# Power.net
KiCad netlist of a schematic drawn in Altium Designer
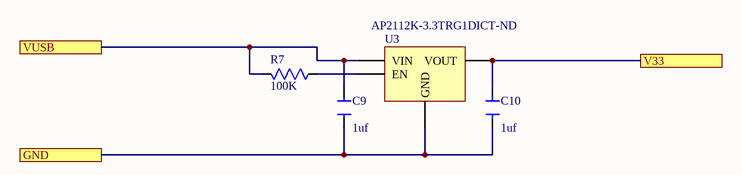
[diagram p0: Power.SchDoc]

(export (version "E")
  (design (tool "Eeschema 10.0.6"))
  (components
    (comp (ref "C9")
      (value "1uf")
      (footprint "CAP_0402")
      (fields (field (name "Comment") "Cap"))
      (libsource (lib "ZGR") (part "Cap"))
    )
    (comp (ref "C10")
      (value "1uf")
      (footprint "CAP_0402")
      (fields (field (name "Comment") "Cap"))
      (libsource (lib "ZGR") (part "Cap"))
    )
    (comp (ref "R7")
      (value "100K")
      (footprint "RES_0402")
      (fields (field (name "Comment") "Res"))
      (libsource (lib "ZGR") (part "Res"))
    )
    (comp (ref "U3")
      (value "AP2112K-3.3TRG1")
      (footprint "SOT23-5")
      (description "IC REG LINEAR 3.3V 600MA SOT23-5")
      (fields
        (field (name "MANUFACTURER") "Diodes")
        (field (name "SUPPLIER PART NUMBER 1") "AP2112K-3.3TRG1DICT-ND")
      )
      (libsource (lib "ZGR") (part "AP2112K-3.3TRG1"))
    )
  )
  (nets
    (net (code "1") (name "/GND") (class "Default")
      (node (ref "C10") (pin "2") (pinfunction "2_2") (pintype "passive"))
      (node (ref "C9") (pin "2") (pinfunction "2_2") (pintype "passive"))
      (node (ref "U3") (pin "3") (pinfunction "GND_3") (pintype "power_in"))
    )
    (net (code "2") (name "/V33") (class "Default")
      (node (ref "C10") (pin "1") (pinfunction "1_1") (pintype "passive"))
      (node (ref "U3") (pin "4") (pinfunction "VOUT_4") (pintype "power_in"))
    )
    (net (code "3") (name "/VUSB") (class "Default")
      (node (ref "C9") (pin "1") (pinfunction "1_1") (pintype "passive"))
      (node (ref "R7") (pin "1") (pinfunction "1_1") (pintype "passive"))
      (node (ref "U3") (pin "1") (pinfunction "VIN_1") (pintype "power_in"))
    )
    (net (code "4") (name "Net-(U3-EN)") (class "Default")
      (node (ref "R7") (pin "2") (pinfunction "2_2") (pintype "passive"))
      (node (ref "U3") (pin "2") (pinfunction "EN_2") (pintype "passive"))
    )
  )
)
